# Mcu_at89s52.net
KiCad netlist of a schematic drawn in Altium Designer
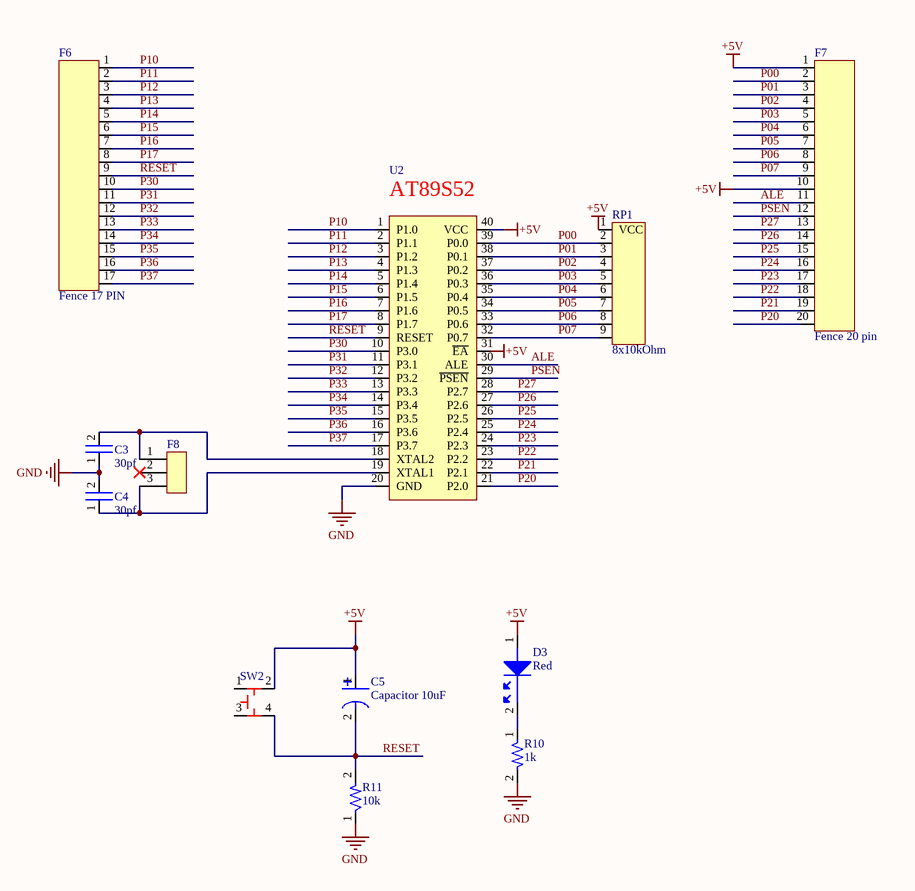
[diagram p0: Mcu_at89s52.SchDoc]

(export (version "E")
  (design (tool "Eeschema 10.0.6"))
  (components
    (comp (ref "C3")
      (value "30pf")
      (footprint "CAP_30pF")
      (description "Tụ hóa 33pf 50V")
      (libsource (lib "Schlib2") (part "Capacitor 33pf"))
    )
    (comp (ref "C4")
      (value "30pf")
      (footprint "CAP_30pF")
      (description "Tụ hóa 33pf 50V")
      (libsource (lib "Schlib2") (part "Capacitor 33pf"))
    )
    (comp (ref "C5")
      (value "Capacitor 10uF")
      (footprint "Capacitor 10uF 50V")
      (description "Tụ hóa 10uF 55V")
      (libsource (lib "Schlib2") (part "Capacitor 10uF"))
    )
    (comp (ref "D3")
      (value "Red")
      (footprint "LED - 3mm")
      (description "LED 5mm")
      (libsource (lib "Schlib2") (part "LED"))
    )
    (comp (ref "F6")
      (value "Fence 17 PIN")
      (footprint "Fence 17PIN")
      (libsource (lib "Schlib2") (part "Fence 17 PIN"))
    )
    (comp (ref "F7")
      (value "Fence 20 pin")
      (footprint "Fence 20PIN")
      (libsource (lib "Schlib2") (part "Fence 20 pin"))
    )
    (comp (ref "F8")
      (value "Fence 3 pin")
      (footprint "Fence 3pin_female")
      (description "hàng rào male 6 chân")
      (libsource (lib "Schlib2") (part "Fence 3 pin"))
    )
    (comp (ref "R10")
      (value "1k")
      (footprint "RESISTOR 1W")
      (description "dien tro")
      (libsource (lib "Schlib2") (part "Resistor"))
    )
    (comp (ref "R11")
      (value "10k")
      (footprint "RESISTOR 10k_0.5W")
      (description "dien tro")
      (libsource (lib "Schlib2") (part "Resistor"))
    )
    (comp (ref "RP1")
      (value "8x10kOhm")
      (footprint "RES_10K_PACK_9PIN")
      (libsource (lib "Schlib2") (part "Resistor_pack_9pin"))
    )
    (comp (ref "SW2") (value "Sw_4pin") (footprint "SW_4PIN") (libsource (lib "Schlib2") (part "Sw_4pin")))
    (comp (ref "U2")
      (value "Ic_socket_40pin_2.54mm")
      (footprint "IC_SOKET_40PIN")
      (libsource (lib "Schlib2") (part "Ic_socket_40pin_2.54mm"))
    )
  )
  (nets
    (net (code "1") (name "+5V") (class "Default")
      (node (ref "C5") (pin "1") (pinfunction "1_1") (pintype "passive"))
      (node (ref "D3") (pin "1") (pinfunction "1_1") (pintype "passive"))
      (node (ref "F7") (pin "1") (pinfunction "VCC_1") (pintype "passive"))
      (node (ref "F7") (pin "10") (pinfunction "VCC_10") (pintype "passive"))
      (node (ref "RP1") (pin "1") (pinfunction "VCC_1") (pintype "passive"))
      (node (ref "SW2") (pin "2") (pinfunction "2_2") (pintype "passive"))
      (node (ref "U2") (pin "31") (pinfunction "~{EA}_31") (pintype "passive"))
      (node (ref "U2") (pin "40") (pinfunction "VCC_40") (pintype "passive"))
    )
    (net (code "2") (name "/ALE") (class "Default")
      (node (ref "F7") (pin "11") (pinfunction "VCC_11") (pintype "passive"))
      (node (ref "U2") (pin "30") (pinfunction "ALE_30") (pintype "passive"))
    )
    (net (code "3") (name "/P00") (class "Default")
      (node (ref "F7") (pin "2") (pinfunction "VCC_2") (pintype "passive"))
      (node (ref "RP1") (pin "2") (pinfunction "2_2") (pintype "passive"))
      (node (ref "U2") (pin "39") (pinfunction "P0.0_39") (pintype "passive"))
    )
    (net (code "4") (name "/P01") (class "Default")
      (node (ref "F7") (pin "3") (pinfunction "VCC_3") (pintype "passive"))
      (node (ref "RP1") (pin "3") (pinfunction "3_3") (pintype "passive"))
      (node (ref "U2") (pin "38") (pinfunction "P0.1_38") (pintype "passive"))
    )
    (net (code "5") (name "/P02") (class "Default")
      (node (ref "F7") (pin "4") (pinfunction "VCC_4") (pintype "passive"))
      (node (ref "RP1") (pin "4") (pinfunction "4_4") (pintype "passive"))
      (node (ref "U2") (pin "37") (pinfunction "P0.2_37") (pintype "passive"))
    )
    (net (code "6") (name "/P03") (class "Default")
      (node (ref "F7") (pin "5") (pinfunction "VCC_5") (pintype "passive"))
      (node (ref "RP1") (pin "5") (pinfunction "5_5") (pintype "passive"))
      (node (ref "U2") (pin "36") (pinfunction "P0.3_36") (pintype "passive"))
    )
    (net (code "7") (name "/P04") (class "Default")
      (node (ref "F7") (pin "6") (pinfunction "VCC_6") (pintype "passive"))
      (node (ref "RP1") (pin "6") (pinfunction "6_6") (pintype "passive"))
      (node (ref "U2") (pin "35") (pinfunction "P0.4_35") (pintype "passive"))
    )
    (net (code "8") (name "/P05") (class "Default")
      (node (ref "F7") (pin "7") (pinfunction "VCC_7") (pintype "passive"))
      (node (ref "RP1") (pin "7") (pinfunction "7_7") (pintype "passive"))
      (node (ref "U2") (pin "34") (pinfunction "P0.5_34") (pintype "passive"))
    )
    (net (code "9") (name "/P06") (class "Default")
      (node (ref "F7") (pin "8") (pinfunction "VCC_8") (pintype "passive"))
      (node (ref "RP1") (pin "8") (pinfunction "8_8") (pintype "passive"))
      (node (ref "U2") (pin "33") (pinfunction "P0.6_33") (pintype "passive"))
    )
    (net (code "10") (name "/P07") (class "Default")
      (node (ref "F7") (pin "9") (pinfunction "VCC_9") (pintype "passive"))
      (node (ref "RP1") (pin "9") (pinfunction "9_9") (pintype "passive"))
      (node (ref "U2") (pin "32") (pinfunction "P0.7_32") (pintype "passive"))
    )
    (net (code "11") (name "/P10") (class "Default")
      (node (ref "F6") (pin "1") (pinfunction "VCC_1") (pintype "passive"))
      (node (ref "U2") (pin "1") (pinfunction "P1.0_1") (pintype "passive"))
    )
    (net (code "12") (name "/P11") (class "Default")
      (node (ref "F6") (pin "2") (pinfunction "VCC_2") (pintype "passive"))
      (node (ref "U2") (pin "2") (pinfunction "P1.1_2") (pintype "passive"))
    )
    (net (code "13") (name "/P12") (class "Default")
      (node (ref "F6") (pin "3") (pinfunction "VCC_3") (pintype "passive"))
      (node (ref "U2") (pin "3") (pinfunction "P1.2_3") (pintype "passive"))
    )
    (net (code "14") (name "/P13") (class "Default")
      (node (ref "F6") (pin "4") (pinfunction "VCC_4") (pintype "passive"))
      (node (ref "U2") (pin "4") (pinfunction "P1.3_4") (pintype "passive"))
    )
    (net (code "15") (name "/P14") (class "Default")
      (node (ref "F6") (pin "5") (pinfunction "VCC_5") (pintype "passive"))
      (node (ref "U2") (pin "5") (pinfunction "P1.4_5") (pintype "passive"))
    )
    (net (code "16") (name "/P15") (class "Default")
      (node (ref "F6") (pin "6") (pinfunction "VCC_6") (pintype "passive"))
      (node (ref "U2") (pin "6") (pinfunction "P1.5_6") (pintype "passive"))
    )
    (net (code "17") (name "/P16") (class "Default")
      (node (ref "F6") (pin "7") (pinfunction "VCC_7") (pintype "passive"))
      (node (ref "U2") (pin "7") (pinfunction "P1.6_7") (pintype "passive"))
    )
    (net (code "18") (name "/P17") (class "Default")
      (node (ref "F6") (pin "8") (pinfunction "VCC_8") (pintype "passive"))
      (node (ref "U2") (pin "8") (pinfunction "P1.7_8") (pintype "passive"))
    )
    (net (code "19") (name "/P20") (class "Default")
      (node (ref "F7") (pin "20") (pinfunction "VCC_20") (pintype "passive"))
      (node (ref "U2") (pin "21") (pinfunction "P2.0_21") (pintype "passive"))
    )
    (net (code "20") (name "/P21") (class "Default")
      (node (ref "F7") (pin "19") (pinfunction "VCC_19") (pintype "passive"))
      (node (ref "U2") (pin "22") (pinfunction "P2.1_22") (pintype "passive"))
    )
    (net (code "21") (name "/P22") (class "Default")
      (node (ref "F7") (pin "18") (pinfunction "VCC_18") (pintype "passive"))
      (node (ref "U2") (pin "23") (pinfunction "P2.2_23") (pintype "passive"))
    )
    (net (code "22") (name "/P23") (class "Default")
      (node (ref "F7") (pin "17") (pinfunction "VCC_17") (pintype "passive"))
      (node (ref "U2") (pin "24") (pinfunction "P2.3_24") (pintype "passive"))
    )
    (net (code "23") (name "/P24") (class "Default")
      (node (ref "F7") (pin "16") (pinfunction "VCC_16") (pintype "passive"))
      (node (ref "U2") (pin "25") (pinfunction "P2.4_25") (pintype "passive"))
    )
    (net (code "24") (name "/P25") (class "Default")
      (node (ref "F7") (pin "15") (pinfunction "VCC_15") (pintype "passive"))
      (node (ref "U2") (pin "26") (pinfunction "P2.5_26") (pintype "passive"))
    )
    (net (code "25") (name "/P26") (class "Default")
      (node (ref "F7") (pin "14") (pinfunction "VCC_14") (pintype "passive"))
      (node (ref "U2") (pin "27") (pinfunction "P2.6_27") (pintype "passive"))
    )
    (net (code "26") (name "/P27") (class "Default")
      (node (ref "F7") (pin "13") (pinfunction "VCC_13") (pintype "passive"))
      (node (ref "U2") (pin "28") (pinfunction "P2.7_28") (pintype "passive"))
    )
    (net (code "27") (name "/P30") (class "Default")
      (node (ref "F6") (pin "10") (pinfunction "VCC_10") (pintype "passive"))
      (node (ref "U2") (pin "10") (pinfunction "P3.0_10") (pintype "passive"))
    )
    (net (code "28") (name "/P31") (class "Default")
      (node (ref "F6") (pin "11") (pinfunction "VCC_11") (pintype "passive"))
      (node (ref "U2") (pin "11") (pinfunction "P3.1_11") (pintype "passive"))
    )
    (net (code "29") (name "/P32") (class "Default")
      (node (ref "F6") (pin "12") (pinfunction "VCC_12") (pintype "passive"))
      (node (ref "U2") (pin "12") (pinfunction "P3.2_12") (pintype "passive"))
    )
    (net (code "30") (name "/P33") (class "Default")
      (node (ref "F6") (pin "13") (pinfunction "VCC_13") (pintype "passive"))
      (node (ref "U2") (pin "13") (pinfunction "P3.3_13") (pintype "passive"))
    )
    (net (code "31") (name "/P34") (class "Default")
      (node (ref "F6") (pin "14") (pinfunction "VCC_14") (pintype "passive"))
      (node (ref "U2") (pin "14") (pinfunction "P3.4_14") (pintype "passive"))
    )
    (net (code "32") (name "/P35") (class "Default")
      (node (ref "F6") (pin "15") (pinfunction "VCC_15") (pintype "passive"))
      (node (ref "U2") (pin "15") (pinfunction "P3.5_15") (pintype "passive"))
    )
    (net (code "33") (name "/P36") (class "Default")
      (node (ref "F6") (pin "16") (pinfunction "VCC_16") (pintype "passive"))
      (node (ref "U2") (pin "16") (pinfunction "P3.6_16") (pintype "passive"))
    )
    (net (code "34") (name "/P37") (class "Default")
      (node (ref "F6") (pin "17") (pinfunction "VCC_17") (pintype "passive"))
      (node (ref "U2") (pin "17") (pinfunction "P3.7_17") (pintype "passive"))
    )
    (net (code "35") (name "/PSEN") (class "Default")
      (node (ref "F7") (pin "12") (pinfunction "VCC_12") (pintype "passive"))
      (node (ref "U2") (pin "29") (pinfunction "~{PSEN}_29") (pintype "passive"))
    )
    (net (code "36") (name "/RESET") (class "Default")
      (node (ref "C5") (pin "2") (pinfunction "2_2") (pintype "passive"))
      (node (ref "F6") (pin "9") (pinfunction "VCC_9") (pintype "passive"))
      (node (ref "R11") (pin "2") (pinfunction "2_2") (pintype "passive"))
      (node (ref "SW2") (pin "4") (pinfunction "4_4") (pintype "passive"))
      (node (ref "U2") (pin "9") (pinfunction "RESET_9") (pintype "passive"))
    )
    (net (code "37") (name "GND") (class "Default")
      (node (ref "C3") (pin "1") (pinfunction "1_1") (pintype "passive"))
      (node (ref "C4") (pin "2") (pinfunction "2_2") (pintype "passive"))
      (node (ref "R10") (pin "2") (pinfunction "2_2") (pintype "passive"))
      (node (ref "R11") (pin "1") (pinfunction "1_1") (pintype "passive"))
      (node (ref "U2") (pin "20") (pinfunction "GND_20") (pintype "passive"))
    )
    (net (code "38") (name "Net-(D3-Pad2)") (class "Default")
      (node (ref "D3") (pin "2") (pinfunction "2_2") (pintype "passive"))
      (node (ref "R10") (pin "1") (pinfunction "1_1") (pintype "passive"))
    )
    (net (code "39") (name "Net-(U2-XTAL1)") (class "Default")
      (node (ref "C4") (pin "1") (pinfunction "1_1") (pintype "passive"))
      (node (ref "F8") (pin "3") (pinfunction "3_3") (pintype "passive"))
      (node (ref "U2") (pin "19") (pinfunction "XTAL1_19") (pintype "passive"))
    )
    (net (code "40") (name "Net-(U2-XTAL2)") (class "Default")
      (node (ref "C3") (pin "2") (pinfunction "2_2") (pintype "passive"))
      (node (ref "F8") (pin "1") (pinfunction "1_1") (pintype "passive"))
      (node (ref "U2") (pin "18") (pinfunction "XTAL2_18") (pintype "passive"))
    )
    (net (code "41") (name "unconnected-(F8-Pad2)") (class "Default")
      (node (ref "F8") (pin "2") (pinfunction "2_2") (pintype "passive+no_connect"))
    )
    (net (code "42") (name "unconnected-(SW2-Pad1)") (class "Default")
      (node (ref "SW2") (pin "1") (pinfunction "1_1") (pintype "passive"))
    )
    (net (code "43") (name "unconnected-(SW2-Pad3)") (class "Default")
      (node (ref "SW2") (pin "3") (pinfunction "3_3") (pintype "passive"))
    )
  )
)
